# Sensor_Module_0x08_Dual_Temperatures_2xD.net
KiCad netlist of a schematic drawn in EAGLE
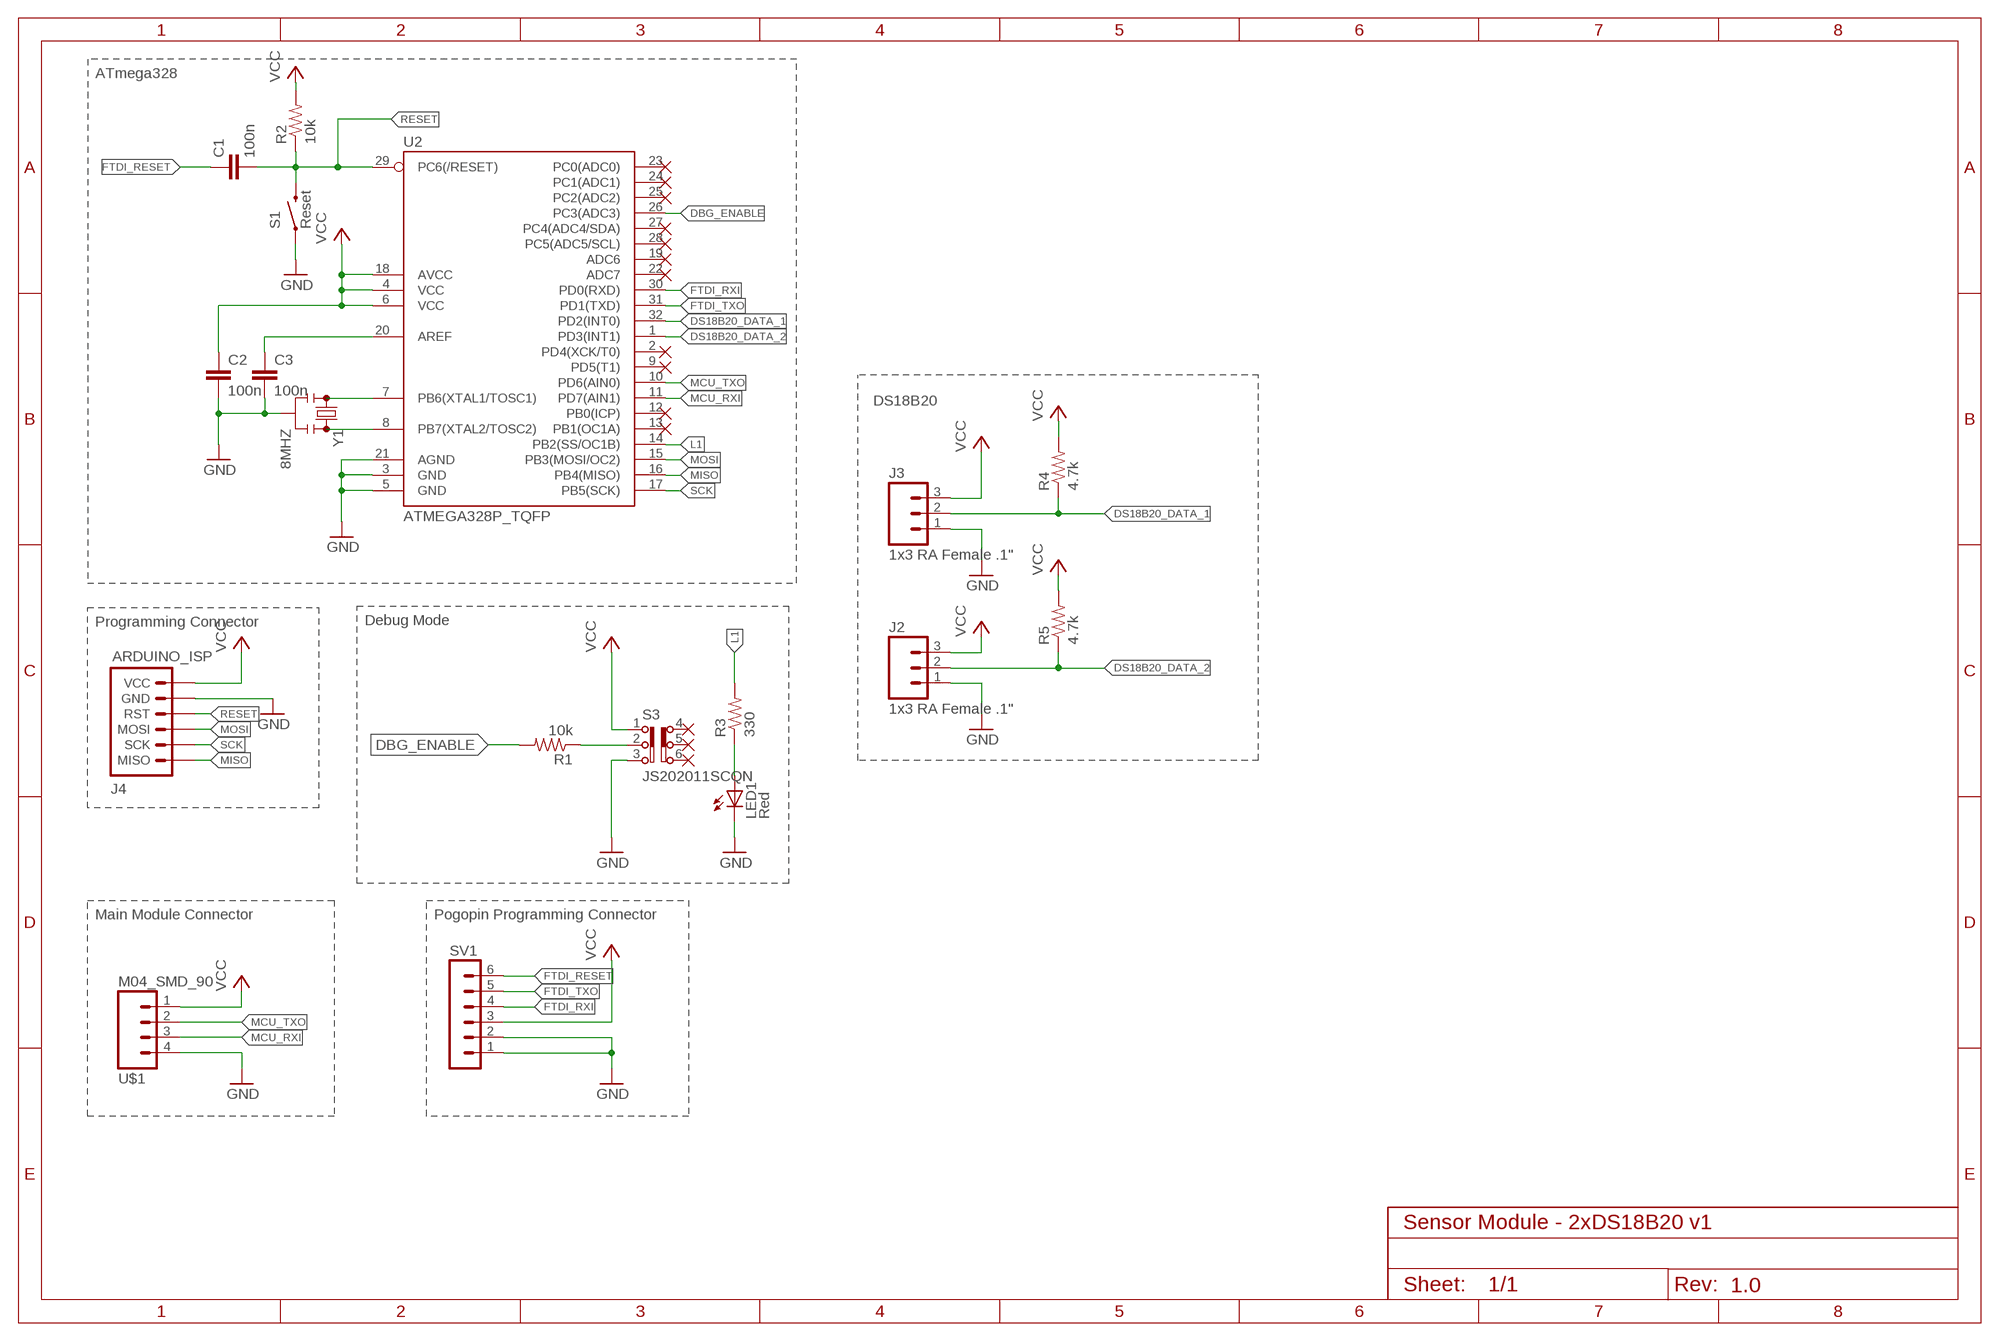
[diagram p0: schematic, sheet 1]

(export (version "E")
  (design (tool "Eeschema 10.0.6"))
  (components
    (comp (ref "C1")
      (value "100n")
      (footprint "eagle-import:C0805")
      (libsource (lib "eagle-import") (part "C"))
    )
    (comp (ref "C2")
      (value "100n")
      (footprint "eagle-import:C0805")
      (libsource (lib "eagle-import") (part "C"))
    )
    (comp (ref "C3")
      (value "100n")
      (footprint "eagle-import:C0805")
      (libsource (lib "eagle-import") (part "C"))
    )
    (comp (ref "J2")
      (value "1x3 RA Female .1\"")
      (footprint "eagle-import:1X03_SMD_RA_FEMALE")
      (libsource (lib "eagle-import") (part "M03SMD_RA_FEMALE"))
    )
    (comp (ref "J3")
      (value "1x3 RA Female .1\"")
      (footprint "eagle-import:1X03_SMD_RA_FEMALE")
      (libsource (lib "eagle-import") (part "M03SMD_RA_FEMALE"))
    )
    (comp (ref "J4")
      (value "ARDUINO_ISP")
      (footprint "eagle-import:M-2X3")
      (libsource (lib "eagle-import") (part "ARDUINO_ISP"))
    )
    (comp (ref "LED1")
      (value "Red")
      (footprint "eagle-import:SML0805")
      (libsource (lib "eagle-import") (part "LEDSML0805"))
    )
    (comp (ref "R1")
      (value "10k")
      (footprint "eagle-import:0805")
      (libsource (lib "eagle-import") (part "RESISTOR0805-RES"))
    )
    (comp (ref "R2")
      (value "10k")
      (footprint "eagle-import:0805")
      (libsource (lib "eagle-import") (part "RESISTOR0805-RES"))
    )
    (comp (ref "R3")
      (value "330")
      (footprint "eagle-import:0805")
      (libsource (lib "eagle-import") (part "RESISTOR0805-RES"))
    )
    (comp (ref "R4")
      (value "4.7k")
      (footprint "eagle-import:0805")
      (libsource (lib "eagle-import") (part "RESISTOR0805-RES"))
    )
    (comp (ref "R5")
      (value "4.7k")
      (footprint "eagle-import:0805")
      (libsource (lib "eagle-import") (part "RESISTOR0805-RES"))
    )
    (comp (ref "S1")
      (value "Reset")
      (footprint "eagle-import:M-PUSHBUTTON-SMD")
      (libsource (lib "eagle-import") (part "PUSHBUTTON"))
    )
    (comp (ref "S3")
      (value "JS202011SCQN")
      (footprint "eagle-import:JS202011SCQN")
      (libsource (lib "eagle-import") (part "JS202011SCQN"))
    )
    (comp (ref "SV1")
      (value "MA06-1")
      (footprint "eagle-import:MA06-1")
      (libsource (lib "eagle-import") (part "MA06-1"))
    )
    (comp (ref "U$1")
      (value "M04_SMD_90")
      (footprint "eagle-import:M04_SMD_90")
      (libsource (lib "eagle-import") (part "M04_SMD_90"))
    )
    (comp (ref "U2")
      (value "ATMEGA328P_TQFP")
      (footprint "eagle-import:TQFP32-08")
      (libsource (lib "eagle-import") (part "ATMEGA328P_TQFP"))
    )
    (comp (ref "Y1")
      (value "8MHZ")
      (footprint "eagle-import:RESONATOR-SMD")
      (libsource (lib "eagle-import") (part "RESONATOR8MHZ"))
    )
  )
  (nets
    (net (code "1") (name "DBG_ENABLE") (class "Default")
      (node (ref "R1") (pin "2") (pinfunction "2_2") (pintype "passive"))
      (node (ref "U2") (pin "26") (pinfunction "PC3(ADC3)_26") (pintype "bidirectional"))
    )
    (net (code "2") (name "DS18B20_DATA_1") (class "Default")
      (node (ref "J3") (pin "2") (pinfunction "2_2") (pintype "passive"))
      (node (ref "R4") (pin "1") (pinfunction "1_1") (pintype "passive"))
      (node (ref "U2") (pin "32") (pinfunction "PD2(INT0)_32") (pintype "bidirectional"))
    )
    (net (code "3") (name "DS18B20_DATA_2") (class "Default")
      (node (ref "J2") (pin "2") (pinfunction "2_2") (pintype "passive"))
      (node (ref "R5") (pin "1") (pinfunction "1_1") (pintype "passive"))
      (node (ref "U2") (pin "1") (pinfunction "PD3(INT1)_1") (pintype "bidirectional"))
    )
    (net (code "4") (name "FTDI_RESET") (class "Default")
      (node (ref "C1") (pin "1") (pinfunction "1_1") (pintype "passive"))
      (node (ref "SV1") (pin "6") (pinfunction "6_6") (pintype "passive"))
    )
    (net (code "5") (name "FTDI_RXI") (class "Default")
      (node (ref "SV1") (pin "4") (pinfunction "4_4") (pintype "passive"))
      (node (ref "U2") (pin "30") (pinfunction "PD0(RXD)_30") (pintype "bidirectional"))
    )
    (net (code "6") (name "FTDI_TXO") (class "Default")
      (node (ref "SV1") (pin "5") (pinfunction "5_5") (pintype "passive"))
      (node (ref "U2") (pin "31") (pinfunction "PD1(TXD)_31") (pintype "bidirectional"))
    )
    (net (code "7") (name "GND") (class "Default")
      (node (ref "C2") (pin "2") (pinfunction "2_2") (pintype "passive"))
      (node (ref "C3") (pin "2") (pinfunction "2_2") (pintype "passive"))
      (node (ref "J2") (pin "1") (pinfunction "1_1") (pintype "passive"))
      (node (ref "J3") (pin "1") (pinfunction "1_1") (pintype "passive"))
      (node (ref "J4") (pin "P$5") (pinfunction "GND_P$5") (pintype "passive"))
      (node (ref "LED1") (pin "C") (pinfunction "C_C") (pintype "passive"))
      (node (ref "S1") (pin "1") (pinfunction "LEFT_1") (pintype "passive"))
      (node (ref "S1") (pin "2") (pinfunction "LEFT_2") (pintype "passive"))
      (node (ref "S3") (pin "3") (pinfunction "3_3") (pintype "passive"))
      (node (ref "SV1") (pin "1") (pinfunction "1_1") (pintype "passive"))
      (node (ref "SV1") (pin "2") (pinfunction "2_2") (pintype "passive"))
      (node (ref "U$1") (pin "4") (pinfunction "4_4") (pintype "passive"))
      (node (ref "U2") (pin "21") (pinfunction "AGND_21") (pintype "bidirectional"))
      (node (ref "U2") (pin "3") (pinfunction "GND_3") (pintype "bidirectional"))
      (node (ref "U2") (pin "5") (pinfunction "GND_5") (pintype "bidirectional"))
      (node (ref "Y1") (pin "2") (pinfunction "2_2") (pintype "passive"))
    )
    (net (code "8") (name "L1") (class "Default")
      (node (ref "R3") (pin "2") (pinfunction "2_2") (pintype "passive"))
      (node (ref "U2") (pin "14") (pinfunction "PB2(SS/OC1B)_14") (pintype "bidirectional"))
    )
    (net (code "9") (name "MCU_RXI") (class "Default")
      (node (ref "U$1") (pin "3") (pinfunction "3_3") (pintype "passive"))
      (node (ref "U2") (pin "11") (pinfunction "PD7(AIN1)_11") (pintype "bidirectional"))
    )
    (net (code "10") (name "MCU_TXO") (class "Default")
      (node (ref "U$1") (pin "2") (pinfunction "2_2") (pintype "passive"))
      (node (ref "U2") (pin "10") (pinfunction "PD6(AIN0)_10") (pintype "bidirectional"))
    )
    (net (code "11") (name "MISO") (class "Default")
      (node (ref "J4") (pin "P$1") (pinfunction "MISO_P$1") (pintype "passive"))
      (node (ref "U2") (pin "16") (pinfunction "PB4(MISO)_16") (pintype "bidirectional"))
    )
    (net (code "12") (name "MOSI") (class "Default")
      (node (ref "J4") (pin "P$3") (pinfunction "MOSI_P$3") (pintype "passive"))
      (node (ref "U2") (pin "15") (pinfunction "PB3(MOSI/OC2)_15") (pintype "bidirectional"))
    )
    (net (code "13") (name "Net-(LED1-PadA)") (class "Default")
      (node (ref "LED1") (pin "A") (pinfunction "A_A") (pintype "passive"))
      (node (ref "R3") (pin "1") (pinfunction "1_1") (pintype "passive"))
    )
    (net (code "14") (name "Net-(R1-Pad1)") (class "Default")
      (node (ref "R1") (pin "1") (pinfunction "1_1") (pintype "passive"))
      (node (ref "S3") (pin "2") (pinfunction "2_2") (pintype "passive"))
    )
    (net (code "15") (name "Net-(U2-AREF)") (class "Default")
      (node (ref "C3") (pin "1") (pinfunction "1_1") (pintype "passive"))
      (node (ref "U2") (pin "20") (pinfunction "AREF_20") (pintype "bidirectional"))
    )
    (net (code "16") (name "Net-(U2-PB6(XTAL1{slash}TOSC1))") (class "Default")
      (node (ref "U2") (pin "7") (pinfunction "PB6(XTAL1/TOSC1)_7") (pintype "bidirectional"))
      (node (ref "Y1") (pin "1") (pinfunction "1_1") (pintype "passive"))
    )
    (net (code "17") (name "Net-(U2-PB7(XTAL2{slash}TOSC2))") (class "Default")
      (node (ref "U2") (pin "8") (pinfunction "PB7(XTAL2/TOSC2)_8") (pintype "bidirectional"))
      (node (ref "Y1") (pin "3") (pinfunction "3_3") (pintype "passive"))
    )
    (net (code "18") (name "RESET") (class "Default")
      (node (ref "C1") (pin "2") (pinfunction "2_2") (pintype "passive"))
      (node (ref "J4") (pin "P$4") (pinfunction "RST_P$4") (pintype "passive"))
      (node (ref "R2") (pin "1") (pinfunction "1_1") (pintype "passive"))
      (node (ref "S1") (pin "3") (pinfunction "RIGHT_3") (pintype "passive"))
      (node (ref "S1") (pin "4") (pinfunction "RIGHT_4") (pintype "passive"))
      (node (ref "U2") (pin "29") (pinfunction "PC6(/RESET)_29") (pintype "bidirectional"))
    )
    (net (code "19") (name "SCK") (class "Default")
      (node (ref "J4") (pin "P$2") (pinfunction "SCK_P$2") (pintype "passive"))
      (node (ref "U2") (pin "17") (pinfunction "PB5(SCK)_17") (pintype "bidirectional"))
    )
    (net (code "20") (name "VCC") (class "Default")
      (node (ref "C2") (pin "1") (pinfunction "1_1") (pintype "passive"))
      (node (ref "J2") (pin "3") (pinfunction "3_3") (pintype "passive"))
      (node (ref "J3") (pin "3") (pinfunction "3_3") (pintype "passive"))
      (node (ref "J4") (pin "P$6") (pinfunction "VCC_P$6") (pintype "passive"))
      (node (ref "R2") (pin "2") (pinfunction "2_2") (pintype "passive"))
      (node (ref "R4") (pin "2") (pinfunction "2_2") (pintype "passive"))
      (node (ref "R5") (pin "2") (pinfunction "2_2") (pintype "passive"))
      (node (ref "S3") (pin "1") (pinfunction "1_1") (pintype "passive"))
      (node (ref "SV1") (pin "3") (pinfunction "3_3") (pintype "passive"))
      (node (ref "U$1") (pin "1") (pinfunction "1_1") (pintype "passive"))
      (node (ref "U2") (pin "18") (pinfunction "AVCC_18") (pintype "bidirectional"))
      (node (ref "U2") (pin "4") (pinfunction "VCC_4") (pintype "bidirectional"))
      (node (ref "U2") (pin "6") (pinfunction "VCC_6") (pintype "bidirectional"))
    )
    (net (code "21") (name "unconnected-(S3-Pad4)") (class "Default")
      (node (ref "S3") (pin "4") (pinfunction "4_4") (pintype "passive"))
    )
    (net (code "22") (name "unconnected-(S3-Pad5)") (class "Default")
      (node (ref "S3") (pin "5") (pinfunction "5_5") (pintype "passive"))
    )
    (net (code "23") (name "unconnected-(S3-Pad6)") (class "Default")
      (node (ref "S3") (pin "6") (pinfunction "6_6") (pintype "passive"))
    )
    (net (code "24") (name "unconnected-(U2-ADC6-Pad19)") (class "Default")
      (node (ref "U2") (pin "19") (pinfunction "ADC6_19") (pintype "bidirectional"))
    )
    (net (code "25") (name "unconnected-(U2-ADC7-Pad22)") (class "Default")
      (node (ref "U2") (pin "22") (pinfunction "ADC7_22") (pintype "bidirectional"))
    )
    (net (code "26") (name "unconnected-(U2-PB0(ICP)-Pad12)") (class "Default")
      (node (ref "U2") (pin "12") (pinfunction "PB0(ICP)_12") (pintype "bidirectional"))
    )
    (net (code "27") (name "unconnected-(U2-PB1(OC1A)-Pad13)") (class "Default")
      (node (ref "U2") (pin "13") (pinfunction "PB1(OC1A)_13") (pintype "bidirectional"))
    )
    (net (code "28") (name "unconnected-(U2-PC0(ADC0)-Pad23)") (class "Default")
      (node (ref "U2") (pin "23") (pinfunction "PC0(ADC0)_23") (pintype "bidirectional"))
    )
    (net (code "29") (name "unconnected-(U2-PC1(ADC1)-Pad24)") (class "Default")
      (node (ref "U2") (pin "24") (pinfunction "PC1(ADC1)_24") (pintype "bidirectional"))
    )
    (net (code "30") (name "unconnected-(U2-PC2(ADC2)-Pad25)") (class "Default")
      (node (ref "U2") (pin "25") (pinfunction "PC2(ADC2)_25") (pintype "bidirectional"))
    )
    (net (code "31") (name "unconnected-(U2-PC4(ADC4{slash}SDA)-Pad27)") (class "Default")
      (node (ref "U2") (pin "27") (pinfunction "PC4(ADC4/SDA)_27") (pintype "bidirectional"))
    )
    (net (code "32") (name "unconnected-(U2-PC5(ADC5{slash}SCL)-Pad28)") (class "Default")
      (node (ref "U2") (pin "28") (pinfunction "PC5(ADC5/SCL)_28") (pintype "bidirectional"))
    )
    (net (code "33") (name "unconnected-(U2-PD4(XCK{slash}T0)-Pad2)") (class "Default")
      (node (ref "U2") (pin "2") (pinfunction "PD4(XCK/T0)_2") (pintype "bidirectional"))
    )
    (net (code "34") (name "unconnected-(U2-PD5(T1)-Pad9)") (class "Default")
      (node (ref "U2") (pin "9") (pinfunction "PD5(T1)_9") (pintype "bidirectional"))
    )
  )
)
